# pic_funky.net
KiCad netlist of a schematic drawn in EAGLE
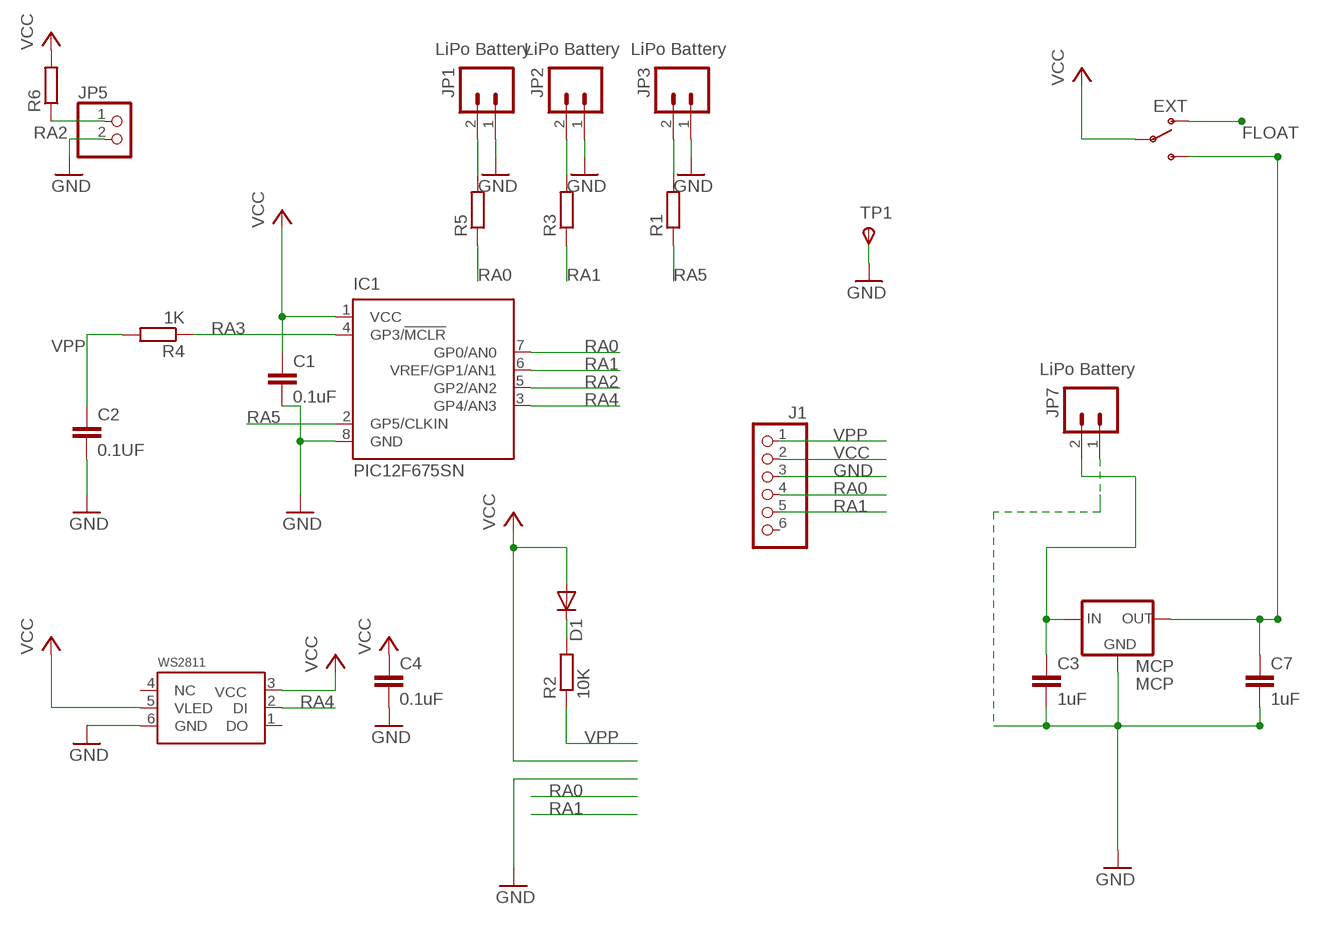
[diagram p0: schematic, sheet 1]

(export (version "E")
  (design (tool "Eeschema 10.0.6"))
  (components
    (comp (ref "C1")
      (value "0.1uF")
      (footprint "eagle-import:C0805")
      (libsource (lib "eagle-import") (part "C-EUC0805"))
    )
    (comp (ref "C2")
      (value "0.1UF")
      (footprint "eagle-import:C0805")
      (libsource (lib "eagle-import") (part "C-EUC0805"))
    )
    (comp (ref "C3")
      (value "1uF")
      (footprint "eagle-import:C0805")
      (libsource (lib "eagle-import") (part "C-EUC0805"))
    )
    (comp (ref "C4")
      (value "0.1uF")
      (footprint "eagle-import:C0805")
      (libsource (lib "eagle-import") (part "C-EUC0805"))
    )
    (comp (ref "C7")
      (value "1uF")
      (footprint "eagle-import:C0805")
      (libsource (lib "eagle-import") (part "C-EUC0805"))
    )
    (comp (ref "D1")
      (value "1N4148")
      (footprint "eagle-import:SOD-323F")
      (libsource (lib "eagle-import") (part "DIODESOD-323F"))
    )
    (comp (ref "IC1")
      (value "PIC12F675SN")
      (footprint "eagle-import:SO-08")
      (fields (field (name "MF") "MICROCHIP") (field (name "MPN") "PIC12F675-E/SN"))
      (libsource (lib "eagle-import") (part "PIC12F675SN"))
    )
    (comp (ref "J1")
      (value "PH1X650MIL")
      (footprint "eagle-import:PH1X6_50MIL")
      (libsource (lib "eagle-import") (part "PH1X650MIL"))
    )
    (comp (ref "JP1")
      (value "LiPo Battery")
      (footprint "eagle-import:JST-2-PTH")
      (libsource (lib "eagle-import") (part "M02JST-PTH-2"))
    )
    (comp (ref "JP2")
      (value "LiPo Battery")
      (footprint "eagle-import:JST-2-PTH")
      (libsource (lib "eagle-import") (part "M02JST-PTH-2"))
    )
    (comp (ref "JP3")
      (value "LiPo Battery")
      (footprint "eagle-import:JST-2-PTH")
      (libsource (lib "eagle-import") (part "M02JST-PTH-2"))
    )
    (comp (ref "JP5")
      (value "PINHD-1X2")
      (footprint "eagle-import:1X02")
      (libsource (lib "eagle-import") (part "PINHD-1X2"))
    )
    (comp (ref "JP7")
      (value "LiPo Battery")
      (footprint "eagle-import:JST-2-PTH")
      (libsource (lib "eagle-import") (part "M02JST-PTH-2"))
    )
    (comp (ref "MCP")
      (value "MCP")
      (footprint "eagle-import:SOT-23")
      (libsource (lib "eagle-import") (part "MCP1700SOT-23"))
    )
    (comp (ref "ON")
      (value "EXT")
      (footprint "eagle-import:SWITCH-SPDT")
      (libsource (lib "eagle-import") (part "SWITCH-SPSTPTH"))
    )
    (comp (ref "R1")
      (value "R-EU_R0805")
      (footprint "eagle-import:R0805")
      (libsource (lib "eagle-import") (part "R-EU_R0805"))
    )
    (comp (ref "R2")
      (value "10K")
      (footprint "eagle-import:R0805")
      (libsource (lib "eagle-import") (part "R-EU_R0805"))
    )
    (comp (ref "R3")
      (value "R-EU_R0805")
      (footprint "eagle-import:R0805")
      (libsource (lib "eagle-import") (part "R-EU_R0805"))
    )
    (comp (ref "R4")
      (value "1K")
      (footprint "eagle-import:R0805")
      (libsource (lib "eagle-import") (part "R-EU_R0805"))
    )
    (comp (ref "R5")
      (value "R-EU_R0805")
      (footprint "eagle-import:R0805")
      (libsource (lib "eagle-import") (part "R-EU_R0805"))
    )
    (comp (ref "R6")
      (value "R-EU_R0805")
      (footprint "eagle-import:R0805")
      (libsource (lib "eagle-import") (part "R-EU_R0805"))
    )
    (comp (ref "TP1")
      (value "TPSTP20R")
      (footprint "eagle-import:TP20R")
      (libsource (lib "eagle-import") (part "TPSTP20R"))
    )
    (comp (ref "WS2811")
      (value "5050WS2811W")
      (footprint "eagle-import:RGBLED5050W")
      (libsource (lib "eagle-import") (part "5050WS2811W"))
    )
  )
  (nets
    (net (code "1") (name "/FLOAT") (class "Default")
      (node (ref "ON") (pin "1") (pinfunction "O_1") (pintype "passive"))
    )
    (net (code "2") (name "/RA0") (class "Default")
      (node (ref "IC1") (pin "7") (pinfunction "GP0/AN0_7") (pintype "bidirectional"))
      (node (ref "J1") (pin "4") (pinfunction "4_4") (pintype "passive"))
      (node (ref "R5") (pin "1") (pinfunction "1_1") (pintype "passive"))
    )
    (net (code "3") (name "/RA1") (class "Default")
      (node (ref "IC1") (pin "6") (pinfunction "VREF/GP1/AN1_6") (pintype "bidirectional"))
      (node (ref "J1") (pin "5") (pinfunction "5_5") (pintype "passive"))
      (node (ref "R3") (pin "1") (pinfunction "1_1") (pintype "passive"))
    )
    (net (code "4") (name "/RA2") (class "Default")
      (node (ref "IC1") (pin "5") (pinfunction "GP2/AN2_5") (pintype "bidirectional"))
      (node (ref "JP5") (pin "1") (pinfunction "1_1") (pintype "passive"))
      (node (ref "R6") (pin "1") (pinfunction "1_1") (pintype "passive"))
    )
    (net (code "5") (name "/RA3") (class "Default")
      (node (ref "IC1") (pin "4") (pinfunction "GP3/~{MCLR}_4") (pintype "input"))
      (node (ref "R4") (pin "1") (pinfunction "1_1") (pintype "passive"))
    )
    (net (code "6") (name "/RA4") (class "Default")
      (node (ref "IC1") (pin "3") (pinfunction "GP4/AN3_3") (pintype "bidirectional"))
      (node (ref "WS2811") (pin "2") (pinfunction "DI_2") (pintype "bidirectional"))
    )
    (net (code "7") (name "/RA5") (class "Default")
      (node (ref "IC1") (pin "2") (pinfunction "GP5/CLKIN_2") (pintype "bidirectional"))
      (node (ref "R1") (pin "1") (pinfunction "1_1") (pintype "passive"))
    )
    (net (code "8") (name "/VPP") (class "Default")
      (node (ref "C2") (pin "1") (pinfunction "1_1") (pintype "passive"))
      (node (ref "J1") (pin "1") (pinfunction "1_1") (pintype "passive"))
      (node (ref "R2") (pin "1") (pinfunction "1_1") (pintype "passive"))
      (node (ref "R4") (pin "2") (pinfunction "2_2") (pintype "passive"))
    )
    (net (code "9") (name "GND") (class "Default")
      (node (ref "C1") (pin "2") (pinfunction "2_2") (pintype "passive"))
      (node (ref "C2") (pin "2") (pinfunction "2_2") (pintype "passive"))
      (node (ref "C3") (pin "2") (pinfunction "2_2") (pintype "passive"))
      (node (ref "C4") (pin "2") (pinfunction "2_2") (pintype "passive"))
      (node (ref "C7") (pin "2") (pinfunction "2_2") (pintype "passive"))
      (node (ref "IC1") (pin "8") (pinfunction "GND_8") (pintype "power_in"))
      (node (ref "J1") (pin "3") (pinfunction "3_3") (pintype "passive"))
      (node (ref "JP1") (pin "1") (pinfunction "1_1") (pintype "passive"))
      (node (ref "JP2") (pin "1") (pinfunction "1_1") (pintype "passive"))
      (node (ref "JP3") (pin "1") (pinfunction "1_1") (pintype "passive"))
      (node (ref "JP5") (pin "2") (pinfunction "2_2") (pintype "passive"))
      (node (ref "JP7") (pin "1") (pinfunction "1_1") (pintype "passive"))
      (node (ref "MCP") (pin "1") (pinfunction "GND_1") (pintype "input"))
      (node (ref "TP1") (pin "TP") (pinfunction "PP_TP") (pintype "input"))
      (node (ref "WS2811") (pin "6") (pinfunction "GND_6") (pintype "bidirectional"))
    )
    (net (code "10") (name "Net-(D1-PadC)") (class "Default")
      (node (ref "D1") (pin "C") (pinfunction "C_C") (pintype "passive"))
      (node (ref "R2") (pin "2") (pinfunction "2_2") (pintype "passive"))
    )
    (net (code "11") (name "Net-(JP1-Pad2)") (class "Default")
      (node (ref "JP1") (pin "2") (pinfunction "2_2") (pintype "passive"))
      (node (ref "R5") (pin "2") (pinfunction "2_2") (pintype "passive"))
    )
    (net (code "12") (name "Net-(JP2-Pad2)") (class "Default")
      (node (ref "JP2") (pin "2") (pinfunction "2_2") (pintype "passive"))
      (node (ref "R3") (pin "2") (pinfunction "2_2") (pintype "passive"))
    )
    (net (code "13") (name "Net-(JP3-Pad2)") (class "Default")
      (node (ref "JP3") (pin "2") (pinfunction "2_2") (pintype "passive"))
      (node (ref "R1") (pin "2") (pinfunction "2_2") (pintype "passive"))
    )
    (net (code "14") (name "Net-(MCP-IN)") (class "Default")
      (node (ref "C3") (pin "1") (pinfunction "1_1") (pintype "passive"))
      (node (ref "JP7") (pin "2") (pinfunction "2_2") (pintype "passive"))
      (node (ref "MCP") (pin "3") (pinfunction "IN_3") (pintype "input"))
    )
    (net (code "15") (name "Net-(MCP-OUT)") (class "Default")
      (node (ref "C7") (pin "1") (pinfunction "1_1") (pintype "passive"))
      (node (ref "MCP") (pin "2") (pinfunction "OUT_2") (pintype "passive"))
      (node (ref "ON") (pin "3") (pinfunction "S_3") (pintype "passive"))
    )
    (net (code "16") (name "VCC") (class "Default")
      (node (ref "C1") (pin "1") (pinfunction "1_1") (pintype "passive"))
      (node (ref "C4") (pin "1") (pinfunction "1_1") (pintype "passive"))
      (node (ref "D1") (pin "A") (pinfunction "A_A") (pintype "passive"))
      (node (ref "IC1") (pin "1") (pinfunction "VCC_1") (pintype "power_in"))
      (node (ref "J1") (pin "2") (pinfunction "2_2") (pintype "passive"))
      (node (ref "ON") (pin "2") (pinfunction "P_2") (pintype "passive"))
      (node (ref "R6") (pin "2") (pinfunction "2_2") (pintype "passive"))
      (node (ref "WS2811") (pin "3") (pinfunction "VCC_3") (pintype "bidirectional"))
      (node (ref "WS2811") (pin "5") (pinfunction "VLED_5") (pintype "bidirectional"))
    )
    (net (code "17") (name "unconnected-(J1-Pad6)") (class "Default")
      (node (ref "J1") (pin "6") (pinfunction "6_6") (pintype "passive"))
    )
    (net (code "18") (name "unconnected-(WS2811-DO-Pad1)") (class "Default")
      (node (ref "WS2811") (pin "1") (pinfunction "DO_1") (pintype "bidirectional"))
    )
    (net (code "19") (name "unconnected-(WS2811-NC-Pad4)") (class "Default")
      (node (ref "WS2811") (pin "4") (pinfunction "NC_4") (pintype "bidirectional"))
    )
  )
)
